# Rangefinder.net
KiCad netlist of a schematic drawn in EAGLE
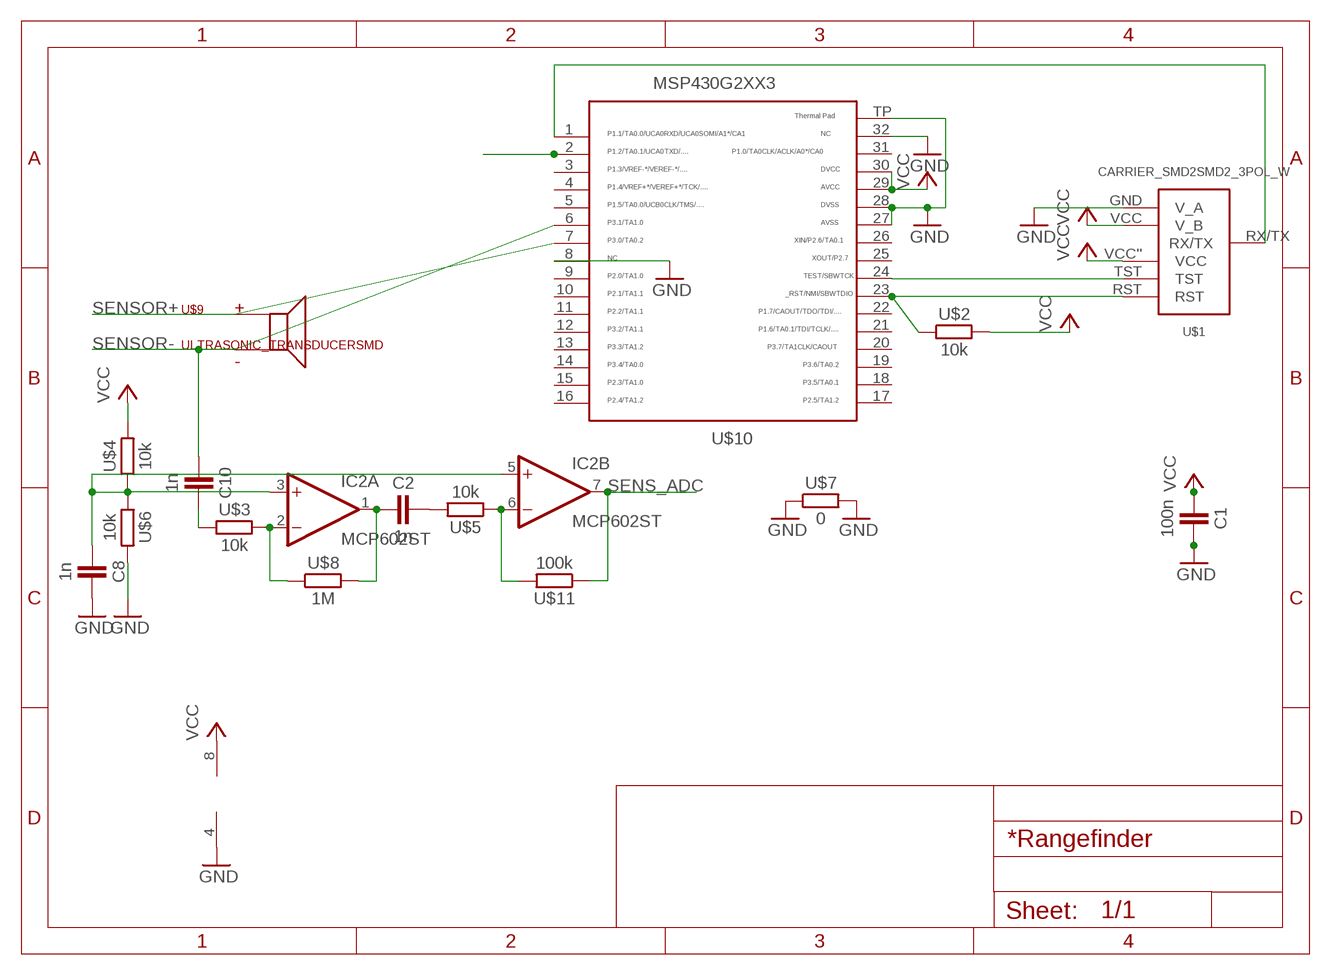
[diagram p0: schematic, sheet 1]

(export (version "E")
  (design (tool "Eeschema 10.0.6"))
  (components
    (comp (ref "C1")
      (value "100n")
      (footprint "eagle-import:603")
      (libsource (lib "eagle-import") (part "CAPACITOR"))
    )
    (comp (ref "C2")
      (value "1n")
      (footprint "eagle-import:603")
      (libsource (lib "eagle-import") (part "CAPACITOR"))
    )
    (comp (ref "C8")
      (value "1n")
      (footprint "eagle-import:603")
      (libsource (lib "eagle-import") (part "CAPACITOR"))
    )
    (comp (ref "C10")
      (value "1n")
      (footprint "eagle-import:603")
      (libsource (lib "eagle-import") (part "CAPACITOR"))
    )
    (comp (ref "IC2")
      (value "MCP602ST")
      (footprint "eagle-import:TSSOP8")
      (libsource (lib "eagle-import") (part "MCP602ST"))
    )
    (comp (ref "U$1")
      (value "CARRIER_SMD2SMD2_3POL_W")
      (footprint "eagle-import:CARRIER_SMD2_WIDE_3POL")
      (libsource (lib "eagle-import") (part "CARRIER_SMD2SMD2_3POL_W"))
    )
    (comp (ref "U$2")
      (value "10k")
      (footprint "eagle-import:603")
      (libsource (lib "eagle-import") (part "RESISTOR0603"))
    )
    (comp (ref "U$3")
      (value "10k")
      (footprint "eagle-import:603")
      (libsource (lib "eagle-import") (part "RESISTOR0603"))
    )
    (comp (ref "U$4")
      (value "10k")
      (footprint "eagle-import:603")
      (libsource (lib "eagle-import") (part "RESISTOR0603"))
    )
    (comp (ref "U$5")
      (value "10k")
      (footprint "eagle-import:603")
      (libsource (lib "eagle-import") (part "RESISTOR0603"))
    )
    (comp (ref "U$6")
      (value "10k")
      (footprint "eagle-import:603")
      (libsource (lib "eagle-import") (part "RESISTOR0603"))
    )
    (comp (ref "U$7")
      (value "0")
      (footprint "eagle-import:603")
      (libsource (lib "eagle-import") (part "RESISTOR0603"))
    )
    (comp (ref "U$8")
      (value "1M")
      (footprint "eagle-import:603")
      (libsource (lib "eagle-import") (part "RESISTOR0603"))
    )
    (comp (ref "U$9")
      (value "ULTRASONIC_TRANSDUCERSMD")
      (footprint "eagle-import:TRANSDUCER2")
      (libsource (lib "eagle-import") (part "ULTRASONIC_TRANSDUCERSMD"))
    )
    (comp (ref "U$10")
      (value "MSP430G2553")
      (footprint "eagle-import:QFN32")
      (libsource (lib "eagle-import") (part "MSP430G2553"))
    )
    (comp (ref "U$11")
      (value "100k")
      (footprint "eagle-import:603")
      (libsource (lib "eagle-import") (part "RESISTOR0603"))
    )
  )
  (nets
    (net (code "1") (name "/SENSOR+") (class "Default")
      (node (ref "U$10") (pin "7") (pinfunction "7_7") (pintype "bidirectional"))
      (node (ref "U$9") (pin "P$3") (pinfunction "P$1_P$3") (pintype "bidirectional"))
    )
    (net (code "2") (name "/SENSOR-") (class "Default")
      (node (ref "C10") (pin "1") (pinfunction "1_1") (pintype "passive"))
      (node (ref "U$10") (pin "6") (pinfunction "6_6") (pintype "bidirectional"))
      (node (ref "U$9") (pin "P$4") (pinfunction "P$2_P$4") (pintype "bidirectional"))
    )
    (net (code "3") (name "/SENS_ADC") (class "Default")
      (node (ref "IC2") (pin "7") (pinfunction "OUT_7") (pintype "output"))
      (node (ref "U$10") (pin "2") (pinfunction "2_2") (pintype "bidirectional"))
      (node (ref "U$11") (pin "1") (pinfunction "1_1") (pintype "passive"))
    )
    (net (code "4") (name "GND") (class "Default")
      (node (ref "C1") (pin "2") (pinfunction "2_2") (pintype "passive"))
      (node (ref "C8") (pin "2") (pinfunction "2_2") (pintype "passive"))
      (node (ref "IC2") (pin "4") (pinfunction "V-_4") (pintype "power_in"))
      (node (ref "U$1") (pin "GND") (pinfunction "V_A_GND") (pintype "bidirectional"))
      (node (ref "U$10") (pin "27") (pinfunction "27_27") (pintype "bidirectional"))
      (node (ref "U$10") (pin "28") (pinfunction "28_28") (pintype "bidirectional"))
      (node (ref "U$10") (pin "32") (pinfunction "32_32") (pintype "bidirectional"))
      (node (ref "U$10") (pin "8") (pinfunction "8_8") (pintype "bidirectional"))
      (node (ref "U$10") (pin "TP") (pinfunction "TP_TP") (pintype "bidirectional"))
      (node (ref "U$6") (pin "2") (pinfunction "2_2") (pintype "passive"))
      (node (ref "U$7") (pin "1") (pinfunction "1_1") (pintype "passive"))
      (node (ref "U$7") (pin "2") (pinfunction "2_2") (pintype "passive"))
    )
    (net (code "5") (name "Net-(C2-Pad2)") (class "Default")
      (node (ref "C2") (pin "2") (pinfunction "2_2") (pintype "passive"))
      (node (ref "U$5") (pin "2") (pinfunction "2_2") (pintype "passive"))
    )
    (net (code "6") (name "Net-(C10-Pad2)") (class "Default")
      (node (ref "C10") (pin "2") (pinfunction "2_2") (pintype "passive"))
      (node (ref "U$3") (pin "1") (pinfunction "1_1") (pintype "passive"))
    )
    (net (code "7") (name "Net-(IC2A-+IN)") (class "Default")
      (node (ref "C8") (pin "1") (pinfunction "1_1") (pintype "passive"))
      (node (ref "IC2") (pin "3") (pinfunction "+IN_3") (pintype "input"))
      (node (ref "IC2") (pin "5") (pinfunction "+IN_5") (pintype "input"))
      (node (ref "U$4") (pin "1") (pinfunction "1_1") (pintype "passive"))
      (node (ref "U$6") (pin "1") (pinfunction "1_1") (pintype "passive"))
    )
    (net (code "8") (name "Net-(IC2A--IN)") (class "Default")
      (node (ref "IC2") (pin "2") (pinfunction "-IN_2") (pintype "input"))
      (node (ref "U$3") (pin "2") (pinfunction "2_2") (pintype "passive"))
      (node (ref "U$8") (pin "1") (pinfunction "1_1") (pintype "passive"))
    )
    (net (code "9") (name "Net-(IC2A-OUT)") (class "Default")
      (node (ref "C2") (pin "1") (pinfunction "1_1") (pintype "passive"))
      (node (ref "IC2") (pin "1") (pinfunction "OUT_1") (pintype "output"))
      (node (ref "U$8") (pin "2") (pinfunction "2_2") (pintype "passive"))
    )
    (net (code "10") (name "Net-(IC2B--IN)") (class "Default")
      (node (ref "IC2") (pin "6") (pinfunction "-IN_6") (pintype "input"))
      (node (ref "U$11") (pin "2") (pinfunction "2_2") (pintype "passive"))
      (node (ref "U$5") (pin "1") (pinfunction "1_1") (pintype "passive"))
    )
    (net (code "11") (name "Net-(U$1-PadRST)") (class "Default")
      (node (ref "U$1") (pin "RST") (pinfunction "RST_RST") (pintype "bidirectional"))
      (node (ref "U$10") (pin "23") (pinfunction "23_23") (pintype "bidirectional"))
      (node (ref "U$2") (pin "1") (pinfunction "1_1") (pintype "passive"))
    )
    (net (code "12") (name "Net-(U$1-PadRX{slash}TX)") (class "Default")
      (node (ref "U$1") (pin "RX/TX") (pinfunction "RX/TX_RX/TX") (pintype "bidirectional"))
      (node (ref "U$10") (pin "1") (pinfunction "1_1") (pintype "bidirectional"))
    )
    (net (code "13") (name "Net-(U$1-PadTST)") (class "Default")
      (node (ref "U$1") (pin "TST") (pinfunction "TST_TST") (pintype "bidirectional"))
      (node (ref "U$10") (pin "24") (pinfunction "24_24") (pintype "bidirectional"))
    )
    (net (code "14") (name "VCC") (class "Default")
      (node (ref "C1") (pin "1") (pinfunction "1_1") (pintype "passive"))
      (node (ref "IC2") (pin "8") (pinfunction "V+_8") (pintype "power_in"))
      (node (ref "U$1") (pin "VCC") (pinfunction "V_B_VCC") (pintype "bidirectional"))
      (node (ref "U$1") (pin "VCC''") (pinfunction "VCC_VCC''") (pintype "bidirectional"))
      (node (ref "U$10") (pin "29") (pinfunction "29_29") (pintype "bidirectional"))
      (node (ref "U$10") (pin "30") (pinfunction "30_30") (pintype "bidirectional"))
      (node (ref "U$2") (pin "2") (pinfunction "2_2") (pintype "passive"))
      (node (ref "U$4") (pin "2") (pinfunction "2_2") (pintype "passive"))
    )
    (net (code "15") (name "unconnected-(U$10-Pad3)") (class "Default")
      (node (ref "U$10") (pin "3") (pinfunction "3_3") (pintype "bidirectional"))
    )
    (net (code "16") (name "unconnected-(U$10-Pad4)") (class "Default")
      (node (ref "U$10") (pin "4") (pinfunction "4_4") (pintype "bidirectional"))
    )
    (net (code "17") (name "unconnected-(U$10-Pad5)") (class "Default")
      (node (ref "U$10") (pin "5") (pinfunction "5_5") (pintype "bidirectional"))
    )
    (net (code "18") (name "unconnected-(U$10-Pad9)") (class "Default")
      (node (ref "U$10") (pin "9") (pinfunction "9_9") (pintype "bidirectional"))
    )
    (net (code "19") (name "unconnected-(U$10-Pad10)") (class "Default")
      (node (ref "U$10") (pin "10") (pinfunction "10_10") (pintype "bidirectional"))
    )
    (net (code "20") (name "unconnected-(U$10-Pad11)") (class "Default")
      (node (ref "U$10") (pin "11") (pinfunction "11_11") (pintype "bidirectional"))
    )
    (net (code "21") (name "unconnected-(U$10-Pad12)") (class "Default")
      (node (ref "U$10") (pin "12") (pinfunction "12_12") (pintype "bidirectional"))
    )
    (net (code "22") (name "unconnected-(U$10-Pad13)") (class "Default")
      (node (ref "U$10") (pin "13") (pinfunction "13_13") (pintype "bidirectional"))
    )
    (net (code "23") (name "unconnected-(U$10-Pad14)") (class "Default")
      (node (ref "U$10") (pin "14") (pinfunction "14_14") (pintype "bidirectional"))
    )
    (net (code "24") (name "unconnected-(U$10-Pad15)") (class "Default")
      (node (ref "U$10") (pin "15") (pinfunction "15_15") (pintype "bidirectional"))
    )
    (net (code "25") (name "unconnected-(U$10-Pad16)") (class "Default")
      (node (ref "U$10") (pin "16") (pinfunction "16_16") (pintype "bidirectional"))
    )
    (net (code "26") (name "unconnected-(U$10-Pad17)") (class "Default")
      (node (ref "U$10") (pin "17") (pinfunction "17_17") (pintype "bidirectional"))
    )
    (net (code "27") (name "unconnected-(U$10-Pad18)") (class "Default")
      (node (ref "U$10") (pin "18") (pinfunction "18_18") (pintype "bidirectional"))
    )
    (net (code "28") (name "unconnected-(U$10-Pad19)") (class "Default")
      (node (ref "U$10") (pin "19") (pinfunction "19_19") (pintype "bidirectional"))
    )
    (net (code "29") (name "unconnected-(U$10-Pad20)") (class "Default")
      (node (ref "U$10") (pin "20") (pinfunction "20_20") (pintype "bidirectional"))
    )
    (net (code "30") (name "unconnected-(U$10-Pad21)") (class "Default")
      (node (ref "U$10") (pin "21") (pinfunction "21_21") (pintype "bidirectional"))
    )
    (net (code "31") (name "unconnected-(U$10-Pad22)") (class "Default")
      (node (ref "U$10") (pin "22") (pinfunction "22_22") (pintype "bidirectional"))
    )
    (net (code "32") (name "unconnected-(U$10-Pad25)") (class "Default")
      (node (ref "U$10") (pin "25") (pinfunction "25_25") (pintype "bidirectional"))
    )
    (net (code "33") (name "unconnected-(U$10-Pad26)") (class "Default")
      (node (ref "U$10") (pin "26") (pinfunction "26_26") (pintype "bidirectional"))
    )
    (net (code "34") (name "unconnected-(U$10-Pad31)") (class "Default")
      (node (ref "U$10") (pin "31") (pinfunction "31_31") (pintype "bidirectional"))
    )
  )
)
